# mcu.net
KiCad netlist of a schematic drawn in Altium Designer
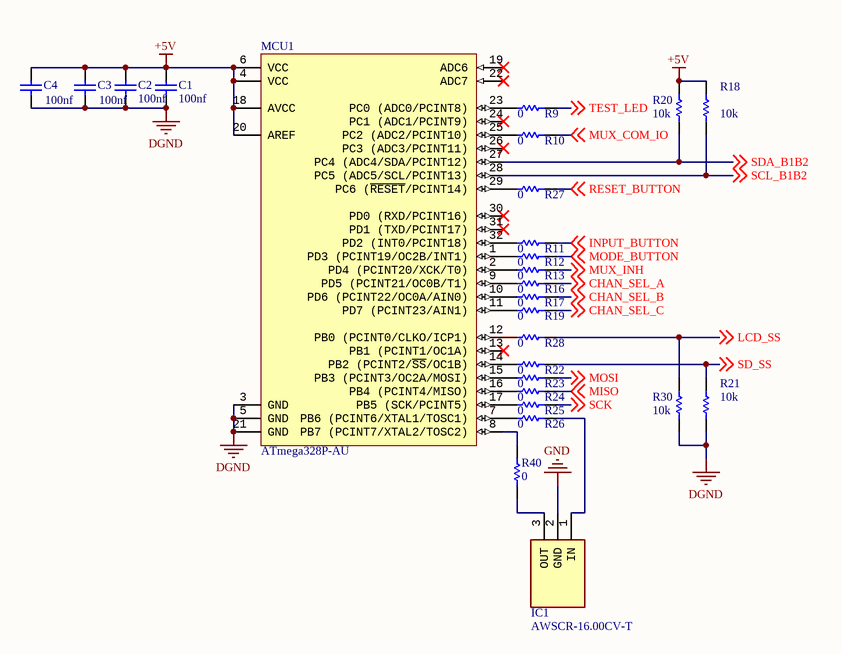
[diagram p0: mcu.SchDoc]

(export (version "E")
  (design (tool "Eeschema 10.0.6"))
  (components
    (comp (ref "C1")
      (value "100nf")
      (footprint "CAPC2013X95X45ML10T25")
      (fields (field (name "MANUFACTURER") "Murata") (field (name "PART NUMBER") "GRM219R71H333KA01D"))
      (libsource (lib "Altium Content Vault") (part "CAP"))
    )
    (comp (ref "C2")
      (value "100nf")
      (footprint "CAPC2013X95X45NL10T25")
      (fields (field (name "MANUFACTURER") "Murata") (field (name "PART NUMBER") "GRM219R71H333KA01D"))
      (libsource (lib "Altium Content Vault") (part "CAP"))
    )
    (comp (ref "C3")
      (value "100nf")
      (footprint "CAPC2013X95X45NL10T25")
      (fields (field (name "MANUFACTURER") "Murata") (field (name "PART NUMBER") "GRM219R71H333KA01D"))
      (libsource (lib "Altium Content Vault") (part "CAP"))
    )
    (comp (ref "C4")
      (value "100nf")
      (footprint "CAPC2013X95X45NL10T25")
      (fields (field (name "MANUFACTURER") "Murata") (field (name "PART NUMBER") "GRM219R71H333KA01D"))
      (libsource (lib "Altium Content Vault") (part "CAP"))
    )
    (comp (ref "IC1")
      (value "AWSCR-16.00CV-T")
      (footprint "AWSCR1600CVT")
      (description "Industrial Grade Ceramic Resonator 16MHz")
      (libsource (lib "Americas- CUAir- Cornell University") (part "AWSCR-16.00CV-T"))
    )
    (comp (ref "MCU1")
      (value "ATmega328P-AU")
      (footprint "32A_M")
      (libsource (lib "Altium Content Vault") (part "MC-8B-ATM48-SQ32"))
    )
    (comp (ref "R9")
      (value "0")
      (footprint "0805")
      (description "RES Thick Film, 0Ω, 0.125W, 150V, 0805")
      (fields (field (name "Comment") "0 (Empty Jumper)"))
      (libsource (lib "Americas- CUAir- Cornell University") (part "0 (Empty Jumper)"))
    )
    (comp (ref "R10")
      (value "0")
      (footprint "0805")
      (description "RES Thick Film, 0Ω, 0.125W, 150V, 0805")
      (fields (field (name "Comment") "0 (Empty Jumper)"))
      (libsource (lib "Americas- CUAir- Cornell University") (part "0 (Empty Jumper)"))
    )
    (comp (ref "R11")
      (value "0")
      (footprint "0805")
      (description "RES Thick Film, 0Ω, 0.125W, 150V, 0805")
      (fields (field (name "Comment") "0 (Empty Jumper)"))
      (libsource (lib "Americas- CUAir- Cornell University") (part "0 (Empty Jumper)"))
    )
    (comp (ref "R12")
      (value "0")
      (footprint "0805")
      (description "RES Thick Film, 0Ω, 0.125W, 150V, 0805")
      (fields (field (name "Comment") "0 (Empty Jumper)"))
      (libsource (lib "Americas- CUAir- Cornell University") (part "0 (Empty Jumper)"))
    )
    (comp (ref "R13")
      (value "0")
      (footprint "0805")
      (description "RES Thick Film, 0Ω, 0.125W, 150V, 0805")
      (fields (field (name "Comment") "0 (Empty Jumper)"))
      (libsource (lib "Americas- CUAir- Cornell University") (part "0 (Empty Jumper)"))
    )
    (comp (ref "R16")
      (value "0")
      (footprint "0805")
      (description "RES Thick Film, 0Ω, 0.125W, 150V, 0805")
      (fields (field (name "Comment") "0 (Empty Jumper)"))
      (libsource (lib "Americas- CUAir- Cornell University") (part "0 (Empty Jumper)"))
    )
    (comp (ref "R17")
      (value "0")
      (footprint "0805")
      (description "RES Thick Film, 0Ω, 0.125W, 150V, 0805")
      (fields (field (name "Comment") "0 (Empty Jumper)"))
      (libsource (lib "Americas- CUAir- Cornell University") (part "0 (Empty Jumper)"))
    )
    (comp (ref "R18")
      (value "10k")
      (footprint "0805")
      (description "RES Thick Film, 10kΩ, 0.125W, 150V, 0805")
      (fields (field (name "JLCPCB BASIC PART") "TRUE") (field (name "JLCPCB PART #") "C17414"))
      (libsource (lib "Americas- CUAir- Cornell University") (part "0 (Empty Jumper)"))
    )
    (comp (ref "R19")
      (value "0")
      (footprint "0805")
      (description "RES Thick Film, 0Ω, 0.125W, 150V, 0805")
      (fields (field (name "Comment") "0 (Empty Jumper)"))
      (libsource (lib "Americas- CUAir- Cornell University") (part "0 (Empty Jumper)"))
    )
    (comp (ref "R20")
      (value "10k")
      (footprint "0805")
      (description "RES Thick Film, 10kΩ, 0.125W, 150V, 0805")
      (fields (field (name "JLCPCB BASIC PART") "TRUE") (field (name "JLCPCB PART #") "C17414"))
      (libsource (lib "Americas- CUAir- Cornell University") (part "0 (Empty Jumper)"))
    )
    (comp (ref "R21")
      (value "10k")
      (footprint "0805")
      (description "RES Thick Film, 10kΩ, 0.125W, 150V, 0805")
      (fields (field (name "JLCPCB BASIC PART") "TRUE") (field (name "JLCPCB PART #") "C17414"))
      (libsource (lib "Americas- CUAir- Cornell University") (part "0 (Empty Jumper)"))
    )
    (comp (ref "R22")
      (value "0")
      (footprint "0805")
      (description "RES Thick Film, 0Ω, 0.125W, 150V, 0805")
      (fields (field (name "Comment") "0 (Empty Jumper)"))
      (libsource (lib "Americas- CUAir- Cornell University") (part "0 (Empty Jumper)"))
    )
    (comp (ref "R23")
      (value "0")
      (footprint "0805")
      (description "RES Thick Film, 0Ω, 0.125W, 150V, 0805")
      (fields (field (name "Comment") "0 (Empty Jumper)"))
      (libsource (lib "Americas- CUAir- Cornell University") (part "0 (Empty Jumper)"))
    )
    (comp (ref "R24")
      (value "0")
      (footprint "0805")
      (description "RES Thick Film, 0Ω, 0.125W, 150V, 0805")
      (fields (field (name "Comment") "0 (Empty Jumper)"))
      (libsource (lib "Americas- CUAir- Cornell University") (part "0 (Empty Jumper)"))
    )
    (comp (ref "R25")
      (value "0")
      (footprint "0805")
      (description "RES Thick Film, 0Ω, 0.125W, 150V, 0805")
      (fields (field (name "Comment") "0 (Empty Jumper)"))
      (libsource (lib "Americas- CUAir- Cornell University") (part "0 (Empty Jumper)"))
    )
    (comp (ref "R26")
      (value "0")
      (footprint "0805")
      (description "RES Thick Film, 0Ω, 0.125W, 150V, 0805")
      (fields (field (name "Comment") "0 (Empty Jumper)"))
      (libsource (lib "Americas- CUAir- Cornell University") (part "0 (Empty Jumper)"))
    )
    (comp (ref "R27")
      (value "0")
      (footprint "0805")
      (description "RES Thick Film, 0Ω, 0.125W, 150V, 0805")
      (fields (field (name "Comment") "0 (Empty Jumper)"))
      (libsource (lib "Americas- CUAir- Cornell University") (part "0 (Empty Jumper)"))
    )
    (comp (ref "R28")
      (value "0")
      (footprint "0805")
      (description "RES Thick Film, 0Ω, 0.125W, 150V, 0805")
      (fields (field (name "Comment") "0 (Empty Jumper)"))
      (libsource (lib "Americas- CUAir- Cornell University") (part "0 (Empty Jumper)"))
    )
    (comp (ref "R30")
      (value "10k")
      (footprint "0805")
      (description "RES Thick Film, 10kΩ, 0.125W, 150V, 0805")
      (fields (field (name "JLCPCB BASIC PART") "TRUE") (field (name "JLCPCB PART #") "C17414"))
      (libsource (lib "Americas- CUAir- Cornell University") (part "0 (Empty Jumper)"))
    )
    (comp (ref "R40")
      (value "0")
      (footprint "0805")
      (description "RES Thick Film, 0Ω, 0.125W, 150V, 0805")
      (fields (field (name "Comment") "0 (Empty Jumper)"))
      (libsource (lib "Americas- CUAir- Cornell University") (part "0 (Empty Jumper)"))
    )
  )
  (nets
    (net (code "1") (name "+5V") (class "Default")
      (node (ref "C1") (pin "2") (pinfunction "2_2") (pintype "passive"))
      (node (ref "C2") (pin "2") (pinfunction "2_2") (pintype "passive"))
      (node (ref "C3") (pin "2") (pinfunction "2_2") (pintype "passive"))
      (node (ref "C4") (pin "2") (pinfunction "2_2") (pintype "passive"))
      (node (ref "MCU1") (pin "18") (pinfunction "AVCC_18") (pintype "power_in"))
      (node (ref "MCU1") (pin "20") (pinfunction "AREF_20") (pintype "passive"))
      (node (ref "MCU1") (pin "4") (pinfunction "VCC_4") (pintype "power_in"))
      (node (ref "MCU1") (pin "6") (pinfunction "VCC_6") (pintype "power_in"))
      (node (ref "R18") (pin "2") (pinfunction "2_2") (pintype "passive"))
      (node (ref "R20") (pin "2") (pinfunction "2_2") (pintype "passive"))
    )
    (net (code "2") (name "CHAN_SEL_A") (class "Default")
      (node (ref "R16") (pin "2") (pinfunction "2_2") (pintype "passive"))
    )
    (net (code "3") (name "CHAN_SEL_B") (class "Default")
      (node (ref "R17") (pin "2") (pinfunction "2_2") (pintype "passive"))
    )
    (net (code "4") (name "CHAN_SEL_C") (class "Default")
      (node (ref "R19") (pin "2") (pinfunction "2_2") (pintype "passive"))
    )
    (net (code "5") (name "DGND") (class "Default")
      (node (ref "C1") (pin "1") (pinfunction "1_1") (pintype "passive"))
      (node (ref "C2") (pin "1") (pinfunction "1_1") (pintype "passive"))
      (node (ref "C3") (pin "1") (pinfunction "1_1") (pintype "passive"))
      (node (ref "C4") (pin "1") (pinfunction "1_1") (pintype "passive"))
      (node (ref "MCU1") (pin "21") (pinfunction "GND_21") (pintype "power_in"))
      (node (ref "MCU1") (pin "3") (pinfunction "GND_3") (pintype "power_in"))
      (node (ref "MCU1") (pin "5") (pinfunction "GND_5") (pintype "power_in"))
      (node (ref "R21") (pin "1") (pinfunction "1_1") (pintype "passive"))
      (node (ref "R30") (pin "1") (pinfunction "1_1") (pintype "passive"))
    )
    (net (code "6") (name "GND") (class "Default")
      (node (ref "IC1") (pin "2") (pinfunction "GND_2") (pintype "passive"))
    )
    (net (code "7") (name "INPUT_BUTTON") (class "Default")
      (node (ref "R11") (pin "2") (pinfunction "2_2") (pintype "passive"))
    )
    (net (code "8") (name "LCD_SS") (class "Default")
      (node (ref "R28") (pin "2") (pinfunction "2_2") (pintype "passive"))
      (node (ref "R30") (pin "2") (pinfunction "2_2") (pintype "passive"))
    )
    (net (code "9") (name "MISO") (class "Default")
      (node (ref "R24") (pin "2") (pinfunction "2_2") (pintype "passive"))
    )
    (net (code "10") (name "MODE_BUTTON") (class "Default")
      (node (ref "R12") (pin "2") (pinfunction "2_2") (pintype "passive"))
    )
    (net (code "11") (name "MOSI") (class "Default")
      (node (ref "R23") (pin "2") (pinfunction "2_2") (pintype "passive"))
    )
    (net (code "12") (name "MUX_COM_IO") (class "Default")
      (node (ref "R10") (pin "2") (pinfunction "2_2") (pintype "passive"))
    )
    (net (code "13") (name "MUX_INH") (class "Default")
      (node (ref "R13") (pin "2") (pinfunction "2_2") (pintype "passive"))
    )
    (net (code "14") (name "Net-(IC1-IN)") (class "Default")
      (node (ref "IC1") (pin "1") (pinfunction "IN_1") (pintype "passive"))
      (node (ref "R26") (pin "2") (pinfunction "2_2") (pintype "passive"))
    )
    (net (code "15") (name "Net-(IC1-OUT)") (class "Default")
      (node (ref "IC1") (pin "3") (pinfunction "OUT_3") (pintype "passive"))
      (node (ref "R40") (pin "1") (pinfunction "1_1") (pintype "passive"))
    )
    (net (code "16") (name "Net-(MCU1-PB0_(PCINT0{slash}CLKO{slash}ICP1))") (class "Default")
      (node (ref "MCU1") (pin "12") (pinfunction "PB0_(PCINT0/CLKO/ICP1)_12") (pintype "bidirectional"))
      (node (ref "R28") (pin "1") (pinfunction "1_1") (pintype "passive"))
    )
    (net (code "17") (name "Net-(MCU1-PB2_(PCINT2{slash}~{SS}{slash}OC1B))") (class "Default")
      (node (ref "MCU1") (pin "14") (pinfunction "PB2_(PCINT2/~{SS}/OC1B)_14") (pintype "bidirectional"))
      (node (ref "R22") (pin "1") (pinfunction "1_1") (pintype "passive"))
    )
    (net (code "18") (name "Net-(MCU1-PB3_(PCINT3{slash}OC2A{slash}MOSI))") (class "Default")
      (node (ref "MCU1") (pin "15") (pinfunction "PB3_(PCINT3/OC2A/MOSI)_15") (pintype "bidirectional"))
      (node (ref "R23") (pin "1") (pinfunction "1_1") (pintype "passive"))
    )
    (net (code "19") (name "Net-(MCU1-PB4_(PCINT4{slash}MISO))") (class "Default")
      (node (ref "MCU1") (pin "16") (pinfunction "PB4_(PCINT4/MISO)_16") (pintype "bidirectional"))
      (node (ref "R24") (pin "1") (pinfunction "1_1") (pintype "passive"))
    )
    (net (code "20") (name "Net-(MCU1-PB5_(SCK{slash}PCINT5))") (class "Default")
      (node (ref "MCU1") (pin "17") (pinfunction "PB5_(SCK/PCINT5)_17") (pintype "bidirectional"))
      (node (ref "R25") (pin "1") (pinfunction "1_1") (pintype "passive"))
    )
    (net (code "21") (name "Net-(MCU1-PB6_(PCINT6{slash}XTAL1{slash}TOSC1))") (class "Default")
      (node (ref "MCU1") (pin "7") (pinfunction "PB6_(PCINT6/XTAL1/TOSC1)_7") (pintype "bidirectional"))
      (node (ref "R26") (pin "1") (pinfunction "1_1") (pintype "passive"))
    )
    (net (code "22") (name "Net-(MCU1-PB7_(PCINT7{slash}XTAL2{slash}TOSC2))") (class "Default")
      (node (ref "MCU1") (pin "8") (pinfunction "PB7_(PCINT7/XTAL2/TOSC2)_8") (pintype "bidirectional"))
      (node (ref "R40") (pin "2") (pinfunction "2_2") (pintype "passive"))
    )
    (net (code "23") (name "Net-(MCU1-PC0_(ADC0{slash}PCINT8))") (class "Default")
      (node (ref "MCU1") (pin "23") (pinfunction "PC0_(ADC0/PCINT8)_23") (pintype "bidirectional"))
      (node (ref "R9") (pin "1") (pinfunction "1_1") (pintype "passive"))
    )
    (net (code "24") (name "Net-(MCU1-PC2_(ADC2{slash}PCINT10))") (class "Default")
      (node (ref "MCU1") (pin "25") (pinfunction "PC2_(ADC2/PCINT10)_25") (pintype "bidirectional"))
      (node (ref "R10") (pin "1") (pinfunction "1_1") (pintype "passive"))
    )
    (net (code "25") (name "Net-(MCU1-PC6_(~{RESET}{slash}PCINT14))") (class "Default")
      (node (ref "MCU1") (pin "29") (pinfunction "PC6_(~{RESET}/PCINT14)_29") (pintype "bidirectional"))
      (node (ref "R27") (pin "1") (pinfunction "1_1") (pintype "passive"))
    )
    (net (code "26") (name "Net-(MCU1-PD2_(INT0{slash}PCINT18))") (class "Default")
      (node (ref "MCU1") (pin "32") (pinfunction "PD2_(INT0/PCINT18)_32") (pintype "bidirectional"))
      (node (ref "R11") (pin "1") (pinfunction "1_1") (pintype "passive"))
    )
    (net (code "27") (name "Net-(MCU1-PD3_(PCINT19{slash}OC2B{slash}INT1))") (class "Default")
      (node (ref "MCU1") (pin "1") (pinfunction "PD3_(PCINT19/OC2B/INT1)_1") (pintype "bidirectional"))
      (node (ref "R12") (pin "1") (pinfunction "1_1") (pintype "passive"))
    )
    (net (code "28") (name "Net-(MCU1-PD4_(PCINT20{slash}XCK{slash}T0))") (class "Default")
      (node (ref "MCU1") (pin "2") (pinfunction "PD4_(PCINT20/XCK/T0)_2") (pintype "bidirectional"))
      (node (ref "R13") (pin "1") (pinfunction "1_1") (pintype "passive"))
    )
    (net (code "29") (name "Net-(MCU1-PD5_(PCINT21{slash}OC0B{slash}T1))") (class "Default")
      (node (ref "MCU1") (pin "9") (pinfunction "PD5_(PCINT21/OC0B/T1)_9") (pintype "bidirectional"))
      (node (ref "R16") (pin "1") (pinfunction "1_1") (pintype "passive"))
    )
    (net (code "30") (name "Net-(MCU1-PD6_(PCINT22{slash}OC0A{slash}AIN0))") (class "Default")
      (node (ref "MCU1") (pin "10") (pinfunction "PD6_(PCINT22/OC0A/AIN0)_10") (pintype "bidirectional"))
      (node (ref "R17") (pin "1") (pinfunction "1_1") (pintype "passive"))
    )
    (net (code "31") (name "Net-(MCU1-PD7_(PCINT23{slash}AIN1))") (class "Default")
      (node (ref "MCU1") (pin "11") (pinfunction "PD7_(PCINT23/AIN1)_11") (pintype "bidirectional"))
      (node (ref "R19") (pin "1") (pinfunction "1_1") (pintype "passive"))
    )
    (net (code "32") (name "RESET_BUTTON") (class "Default")
      (node (ref "R27") (pin "2") (pinfunction "2_2") (pintype "passive"))
    )
    (net (code "33") (name "SCK") (class "Default")
      (node (ref "R25") (pin "2") (pinfunction "2_2") (pintype "passive"))
    )
    (net (code "34") (name "SCL_B1B2") (class "Default")
      (node (ref "MCU1") (pin "28") (pinfunction "PC5_(ADC5/SCL/PCINT13)_28") (pintype "bidirectional"))
      (node (ref "R18") (pin "1") (pinfunction "1_1") (pintype "passive"))
    )
    (net (code "35") (name "SDA_B1B2") (class "Default")
      (node (ref "MCU1") (pin "27") (pinfunction "PC4_(ADC4/SDA/PCINT12)_27") (pintype "bidirectional"))
      (node (ref "R20") (pin "1") (pinfunction "1_1") (pintype "passive"))
    )
    (net (code "36") (name "SD_SS") (class "Default")
      (node (ref "R21") (pin "2") (pinfunction "2_2") (pintype "passive"))
      (node (ref "R22") (pin "2") (pinfunction "2_2") (pintype "passive"))
    )
    (net (code "37") (name "TEST_LED") (class "Default")
      (node (ref "R9") (pin "2") (pinfunction "2_2") (pintype "passive"))
    )
    (net (code "38") (name "unconnected-(MCU1-ADC6-Pad19)") (class "Default")
      (node (ref "MCU1") (pin "19") (pinfunction "ADC6_19") (pintype "input+no_connect"))
    )
    (net (code "39") (name "unconnected-(MCU1-ADC7-Pad22)") (class "Default")
      (node (ref "MCU1") (pin "22") (pinfunction "ADC7_22") (pintype "input+no_connect"))
    )
    (net (code "40") (name "unconnected-(MCU1-PB1_(PCINT1{slash}OC1A)-Pad13)") (class "Default")
      (node (ref "MCU1") (pin "13") (pinfunction "PB1_(PCINT1/OC1A)_13") (pintype "bidirectional+no_connect"))
    )
    (net (code "41") (name "unconnected-(MCU1-PC1_(ADC1{slash}PCINT9)-Pad24)") (class "Default")
      (node (ref "MCU1") (pin "24") (pinfunction "PC1_(ADC1/PCINT9)_24") (pintype "bidirectional+no_connect"))
    )
    (net (code "42") (name "unconnected-(MCU1-PC3_(ADC3{slash}PCINT11)-Pad26)") (class "Default")
      (node (ref "MCU1") (pin "26") (pinfunction "PC3_(ADC3/PCINT11)_26") (pintype "bidirectional+no_connect"))
    )
    (net (code "43") (name "unconnected-(MCU1-PD0_(RXD{slash}PCINT16)-Pad30)") (class "Default")
      (node (ref "MCU1") (pin "30") (pinfunction "PD0_(RXD/PCINT16)_30") (pintype "bidirectional+no_connect"))
    )
    (net (code "44") (name "unconnected-(MCU1-PD1_(TXD{slash}PCINT17)-Pad31)") (class "Default")
      (node (ref "MCU1") (pin "31") (pinfunction "PD1_(TXD/PCINT17)_31") (pintype "bidirectional+no_connect"))
    )
  )
)
